# mosfet-h-bridge-v1.net
KiCad netlist of a schematic drawn in EAGLE
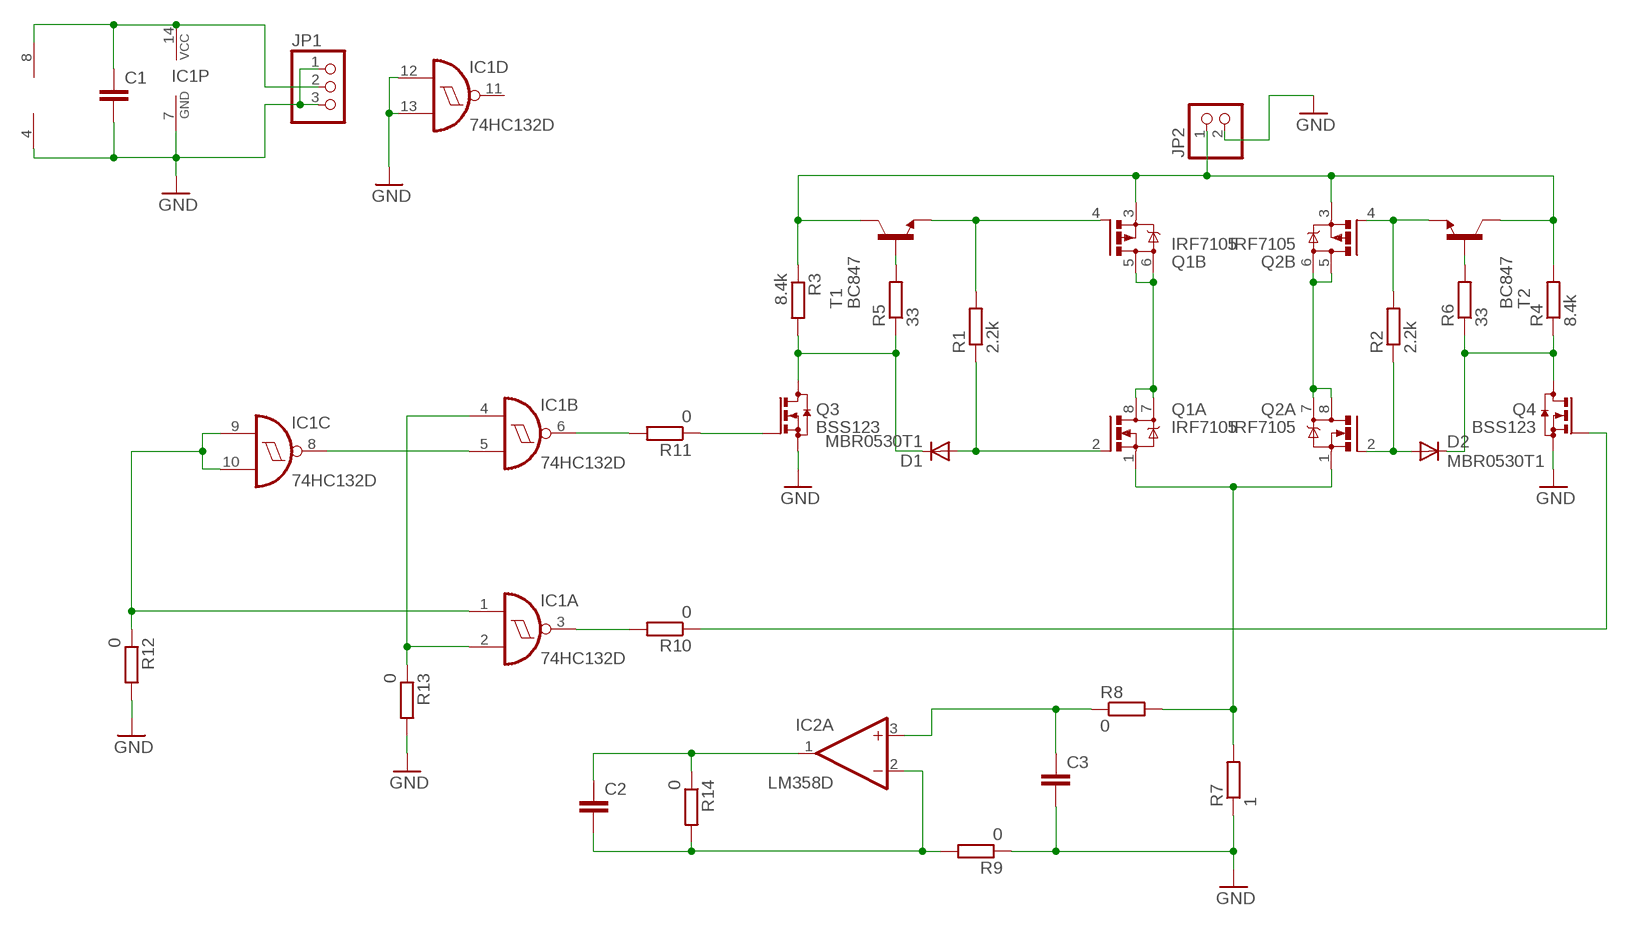
[diagram p0: schematic, sheet 1]

(export (version "E")
  (design (tool "Eeschema 10.0.6"))
  (components
    (comp (ref "C1")
      (value "C-EUC1206K")
      (footprint "eagle-import:C1206K")
      (libsource (lib "eagle-import") (part "C-EUC1206K"))
    )
    (comp (ref "C2")
      (value "C-EUC1206")
      (footprint "eagle-import:C1206")
      (libsource (lib "eagle-import") (part "resistor_C-EUC1206"))
    )
    (comp (ref "C3")
      (value "C-EUC1206")
      (footprint "eagle-import:C1206")
      (libsource (lib "eagle-import") (part "resistor_C-EUC1206"))
    )
    (comp (ref "D1")
      (value "MBR0530T1")
      (footprint "eagle-import:SOD123")
      (libsource (lib "eagle-import") (part "MBR0530T1"))
    )
    (comp (ref "D2")
      (value "MBR0530T1")
      (footprint "eagle-import:SOD123")
      (libsource (lib "eagle-import") (part "MBR0530T1"))
    )
    (comp (ref "IC1")
      (value "74HC132D")
      (footprint "eagle-import:SO14")
      (libsource (lib "eagle-import") (part "74132DHC"))
    )
    (comp (ref "IC2")
      (value "LM358D")
      (footprint "eagle-import:SO08")
      (libsource (lib "eagle-import") (part "LM358D"))
    )
    (comp (ref "JP1")
      (value "PINHD-1X3")
      (footprint "eagle-import:1X03")
      (libsource (lib "eagle-import") (part "PINHD-1X3"))
    )
    (comp (ref "JP2")
      (value "PINHD-1X2")
      (footprint "eagle-import:1X02")
      (libsource (lib "eagle-import") (part "PINHD-1X2"))
    )
    (comp (ref "Q1")
      (value "IRF7105")
      (footprint "eagle-import:SO08")
      (libsource (lib "eagle-import") (part "IRF7105"))
    )
    (comp (ref "Q2")
      (value "IRF7105")
      (footprint "eagle-import:SO08")
      (libsource (lib "eagle-import") (part "IRF7105"))
    )
    (comp (ref "Q3")
      (value "BSS123")
      (footprint "eagle-import:SOT23")
      (libsource (lib "eagle-import") (part "BSS123"))
    )
    (comp (ref "Q4")
      (value "BSS123")
      (footprint "eagle-import:SOT23")
      (libsource (lib "eagle-import") (part "BSS123"))
    )
    (comp (ref "R1")
      (value "2.2k")
      (footprint "eagle-import:R1206S")
      (libsource (lib "eagle-import") (part "R-EU_R1206S"))
    )
    (comp (ref "R2")
      (value "2.2k")
      (footprint "eagle-import:R1206S")
      (libsource (lib "eagle-import") (part "R-EU_R1206S"))
    )
    (comp (ref "R3")
      (value "8.4k")
      (footprint "eagle-import:R1206S")
      (libsource (lib "eagle-import") (part "R-EU_R1206S"))
    )
    (comp (ref "R4")
      (value "8.4k")
      (footprint "eagle-import:R1206S")
      (libsource (lib "eagle-import") (part "R-EU_R1206S"))
    )
    (comp (ref "R5")
      (value "33")
      (footprint "eagle-import:R1206S")
      (libsource (lib "eagle-import") (part "R-EU_R1206S"))
    )
    (comp (ref "R6")
      (value "33")
      (footprint "eagle-import:R1206S")
      (libsource (lib "eagle-import") (part "R-EU_R1206S"))
    )
    (comp (ref "R7")
      (value "1")
      (footprint "eagle-import:R2512")
      (libsource (lib "eagle-import") (part "R-EU_R2512"))
    )
    (comp (ref "R8")
      (value "0")
      (footprint "eagle-import:R1206S")
      (libsource (lib "eagle-import") (part "R-EU_R1206S"))
    )
    (comp (ref "R9")
      (value "0")
      (footprint "eagle-import:R1206S")
      (libsource (lib "eagle-import") (part "R-EU_R1206S"))
    )
    (comp (ref "R10")
      (value "0")
      (footprint "eagle-import:R1206S")
      (libsource (lib "eagle-import") (part "R-EU_R1206S"))
    )
    (comp (ref "R11")
      (value "0")
      (footprint "eagle-import:R1206S")
      (libsource (lib "eagle-import") (part "R-EU_R1206S"))
    )
    (comp (ref "R12")
      (value "0")
      (footprint "eagle-import:R1206S")
      (libsource (lib "eagle-import") (part "R-EU_R1206S"))
    )
    (comp (ref "R13")
      (value "0")
      (footprint "eagle-import:R1206S")
      (libsource (lib "eagle-import") (part "R-EU_R1206S"))
    )
    (comp (ref "R14")
      (value "0")
      (footprint "eagle-import:R1206S")
      (libsource (lib "eagle-import") (part "R-EU_R1206S"))
    )
    (comp (ref "T1")
      (value "BC847")
      (footprint "eagle-import:SOT23")
      (libsource (lib "eagle-import") (part "BC847"))
    )
    (comp (ref "T2")
      (value "BC847")
      (footprint "eagle-import:SOT23")
      (libsource (lib "eagle-import") (part "BC847"))
    )
  )
  (nets
    (net (code "1") (name "GND") (class "Default")
      (node (ref "C1") (pin "2") (pinfunction "2_2") (pintype "passive"))
      (node (ref "C3") (pin "2") (pinfunction "2_2") (pintype "passive"))
      (node (ref "IC1") (pin "12") (pinfunction "I0_12") (pintype "input"))
      (node (ref "IC1") (pin "13") (pinfunction "I1_13") (pintype "input"))
      (node (ref "IC1") (pin "7") (pinfunction "GND_7") (pintype "power_in"))
      (node (ref "IC2") (pin "4") (pinfunction "V-_4") (pintype "power_in"))
      (node (ref "JP1") (pin "1") (pinfunction "1_1") (pintype "passive"))
      (node (ref "JP1") (pin "3") (pinfunction "3_3") (pintype "passive"))
      (node (ref "JP2") (pin "2") (pinfunction "2_2") (pintype "passive"))
      (node (ref "Q3") (pin "2") (pinfunction "S_2") (pintype "passive"))
      (node (ref "Q4") (pin "2") (pinfunction "S_2") (pintype "passive"))
      (node (ref "R12") (pin "2") (pinfunction "2_2") (pintype "passive"))
      (node (ref "R13") (pin "2") (pinfunction "2_2") (pintype "passive"))
      (node (ref "R7") (pin "1") (pinfunction "1_1") (pintype "passive"))
      (node (ref "R9") (pin "1") (pinfunction "1_1") (pintype "passive"))
    )
    (net (code "2") (name "Net-(IC1A-I0)") (class "Default")
      (node (ref "IC1") (pin "1") (pinfunction "I0_1") (pintype "input"))
      (node (ref "IC1") (pin "10") (pinfunction "I1_10") (pintype "input"))
      (node (ref "IC1") (pin "9") (pinfunction "I0_9") (pintype "input"))
      (node (ref "R12") (pin "1") (pinfunction "1_1") (pintype "passive"))
    )
    (net (code "3") (name "Net-(IC1A-I1)") (class "Default")
      (node (ref "IC1") (pin "2") (pinfunction "I1_2") (pintype "input"))
      (node (ref "IC1") (pin "4") (pinfunction "I0_4") (pintype "input"))
      (node (ref "R13") (pin "1") (pinfunction "1_1") (pintype "passive"))
    )
    (net (code "4") (name "Net-(IC1A-O)") (class "Default")
      (node (ref "IC1") (pin "3") (pinfunction "O_3") (pintype "output"))
      (node (ref "R10") (pin "2") (pinfunction "2_2") (pintype "passive"))
    )
    (net (code "5") (name "Net-(IC1B-I1)") (class "Default")
      (node (ref "IC1") (pin "5") (pinfunction "I1_5") (pintype "input"))
      (node (ref "IC1") (pin "8") (pinfunction "O_8") (pintype "output"))
    )
    (net (code "6") (name "Net-(IC1B-O)") (class "Default")
      (node (ref "IC1") (pin "6") (pinfunction "O_6") (pintype "output"))
      (node (ref "R11") (pin "2") (pinfunction "2_2") (pintype "passive"))
    )
    (net (code "7") (name "Net-(IC1E-VCC)") (class "Default")
      (node (ref "C1") (pin "1") (pinfunction "1_1") (pintype "passive"))
      (node (ref "IC1") (pin "14") (pinfunction "VCC_14") (pintype "power_in"))
      (node (ref "IC2") (pin "8") (pinfunction "V+_8") (pintype "power_in"))
      (node (ref "JP1") (pin "2") (pinfunction "2_2") (pintype "passive"))
    )
    (net (code "8") (name "Net-(IC2A-+IN)") (class "Default")
      (node (ref "C3") (pin "1") (pinfunction "1_1") (pintype "passive"))
      (node (ref "IC2") (pin "3") (pinfunction "+IN_3") (pintype "input"))
      (node (ref "R8") (pin "1") (pinfunction "1_1") (pintype "passive"))
    )
    (net (code "9") (name "Net-(IC2A--IN)") (class "Default")
      (node (ref "C2") (pin "2") (pinfunction "2_2") (pintype "passive"))
      (node (ref "IC2") (pin "2") (pinfunction "-IN_2") (pintype "input"))
      (node (ref "R14") (pin "2") (pinfunction "2_2") (pintype "passive"))
      (node (ref "R9") (pin "2") (pinfunction "2_2") (pintype "passive"))
    )
    (net (code "10") (name "Net-(IC2A-OUT)") (class "Default")
      (node (ref "C2") (pin "1") (pinfunction "1_1") (pintype "passive"))
      (node (ref "IC2") (pin "1") (pinfunction "OUT_1") (pintype "output"))
      (node (ref "R14") (pin "1") (pinfunction "1_1") (pintype "passive"))
    )
    (net (code "11") (name "Net-(Q1A-D)") (class "Default")
      (node (ref "Q1") (pin "5") (pinfunction "D_5") (pintype "passive"))
      (node (ref "Q1") (pin "6") (pinfunction "D1_6") (pintype "passive"))
      (node (ref "Q1") (pin "7") (pinfunction "D1_7") (pintype "passive"))
      (node (ref "Q1") (pin "8") (pinfunction "D_8") (pintype "passive"))
    )
    (net (code "12") (name "Net-(Q1A-G)") (class "Default")
      (node (ref "D1") (pin "A") (pinfunction "A_A") (pintype "passive"))
      (node (ref "Q1") (pin "2") (pinfunction "G_2") (pintype "passive"))
      (node (ref "R1") (pin "1") (pinfunction "1_1") (pintype "passive"))
    )
    (net (code "13") (name "Net-(Q1A-S)") (class "Default")
      (node (ref "Q1") (pin "1") (pinfunction "S_1") (pintype "passive"))
      (node (ref "Q2") (pin "1") (pinfunction "S_1") (pintype "passive"))
      (node (ref "R7") (pin "2") (pinfunction "2_2") (pintype "passive"))
      (node (ref "R8") (pin "2") (pinfunction "2_2") (pintype "passive"))
    )
    (net (code "14") (name "Net-(Q1B-G)") (class "Default")
      (node (ref "Q1") (pin "4") (pinfunction "G_4") (pintype "passive"))
      (node (ref "R1") (pin "2") (pinfunction "2_2") (pintype "passive"))
      (node (ref "T1") (pin "2") (pinfunction "E_2") (pintype "passive"))
    )
    (net (code "15") (name "Net-(Q1B-S)") (class "Default")
      (node (ref "JP2") (pin "1") (pinfunction "1_1") (pintype "passive"))
      (node (ref "Q1") (pin "3") (pinfunction "S_3") (pintype "passive"))
      (node (ref "Q2") (pin "3") (pinfunction "S_3") (pintype "passive"))
      (node (ref "R3") (pin "1") (pinfunction "1_1") (pintype "passive"))
      (node (ref "R4") (pin "2") (pinfunction "2_2") (pintype "passive"))
      (node (ref "T1") (pin "3") (pinfunction "C_3") (pintype "passive"))
      (node (ref "T2") (pin "3") (pinfunction "C_3") (pintype "passive"))
    )
    (net (code "16") (name "Net-(Q2A-D)") (class "Default")
      (node (ref "Q2") (pin "5") (pinfunction "D_5") (pintype "passive"))
      (node (ref "Q2") (pin "6") (pinfunction "D1_6") (pintype "passive"))
      (node (ref "Q2") (pin "7") (pinfunction "D1_7") (pintype "passive"))
      (node (ref "Q2") (pin "8") (pinfunction "D_8") (pintype "passive"))
    )
    (net (code "17") (name "Net-(Q2A-G)") (class "Default")
      (node (ref "D2") (pin "A") (pinfunction "A_A") (pintype "passive"))
      (node (ref "Q2") (pin "2") (pinfunction "G_2") (pintype "passive"))
      (node (ref "R2") (pin "1") (pinfunction "1_1") (pintype "passive"))
    )
    (net (code "18") (name "Net-(Q2B-G)") (class "Default")
      (node (ref "Q2") (pin "4") (pinfunction "G_4") (pintype "passive"))
      (node (ref "R2") (pin "2") (pinfunction "2_2") (pintype "passive"))
      (node (ref "T2") (pin "2") (pinfunction "E_2") (pintype "passive"))
    )
    (net (code "19") (name "Net-(Q3-D)") (class "Default")
      (node (ref "D1") (pin "C") (pinfunction "C_C") (pintype "passive"))
      (node (ref "Q3") (pin "3") (pinfunction "D_3") (pintype "passive"))
      (node (ref "R3") (pin "2") (pinfunction "2_2") (pintype "passive"))
      (node (ref "R5") (pin "1") (pinfunction "1_1") (pintype "passive"))
    )
    (net (code "20") (name "Net-(Q3-G)") (class "Default")
      (node (ref "Q3") (pin "1") (pinfunction "G_1") (pintype "passive"))
      (node (ref "R11") (pin "1") (pinfunction "1_1") (pintype "passive"))
    )
    (net (code "21") (name "Net-(Q4-D)") (class "Default")
      (node (ref "D2") (pin "C") (pinfunction "C_C") (pintype "passive"))
      (node (ref "Q4") (pin "3") (pinfunction "D_3") (pintype "passive"))
      (node (ref "R4") (pin "1") (pinfunction "1_1") (pintype "passive"))
      (node (ref "R6") (pin "1") (pinfunction "1_1") (pintype "passive"))
    )
    (net (code "22") (name "Net-(Q4-G)") (class "Default")
      (node (ref "Q4") (pin "1") (pinfunction "G_1") (pintype "passive"))
      (node (ref "R10") (pin "1") (pinfunction "1_1") (pintype "passive"))
    )
    (net (code "23") (name "Net-(T1-B)") (class "Default")
      (node (ref "R5") (pin "2") (pinfunction "2_2") (pintype "passive"))
      (node (ref "T1") (pin "1") (pinfunction "B_1") (pintype "passive"))
    )
    (net (code "24") (name "Net-(T2-B)") (class "Default")
      (node (ref "R6") (pin "2") (pinfunction "2_2") (pintype "passive"))
      (node (ref "T2") (pin "1") (pinfunction "B_1") (pintype "passive"))
    )
    (net (code "25") (name "unconnected-(IC1D-O-Pad11)") (class "Default")
      (node (ref "IC1") (pin "11") (pinfunction "O_11") (pintype "output"))
    )
  )
)
